# footswitch.net
KiCad netlist of a schematic drawn in EAGLE
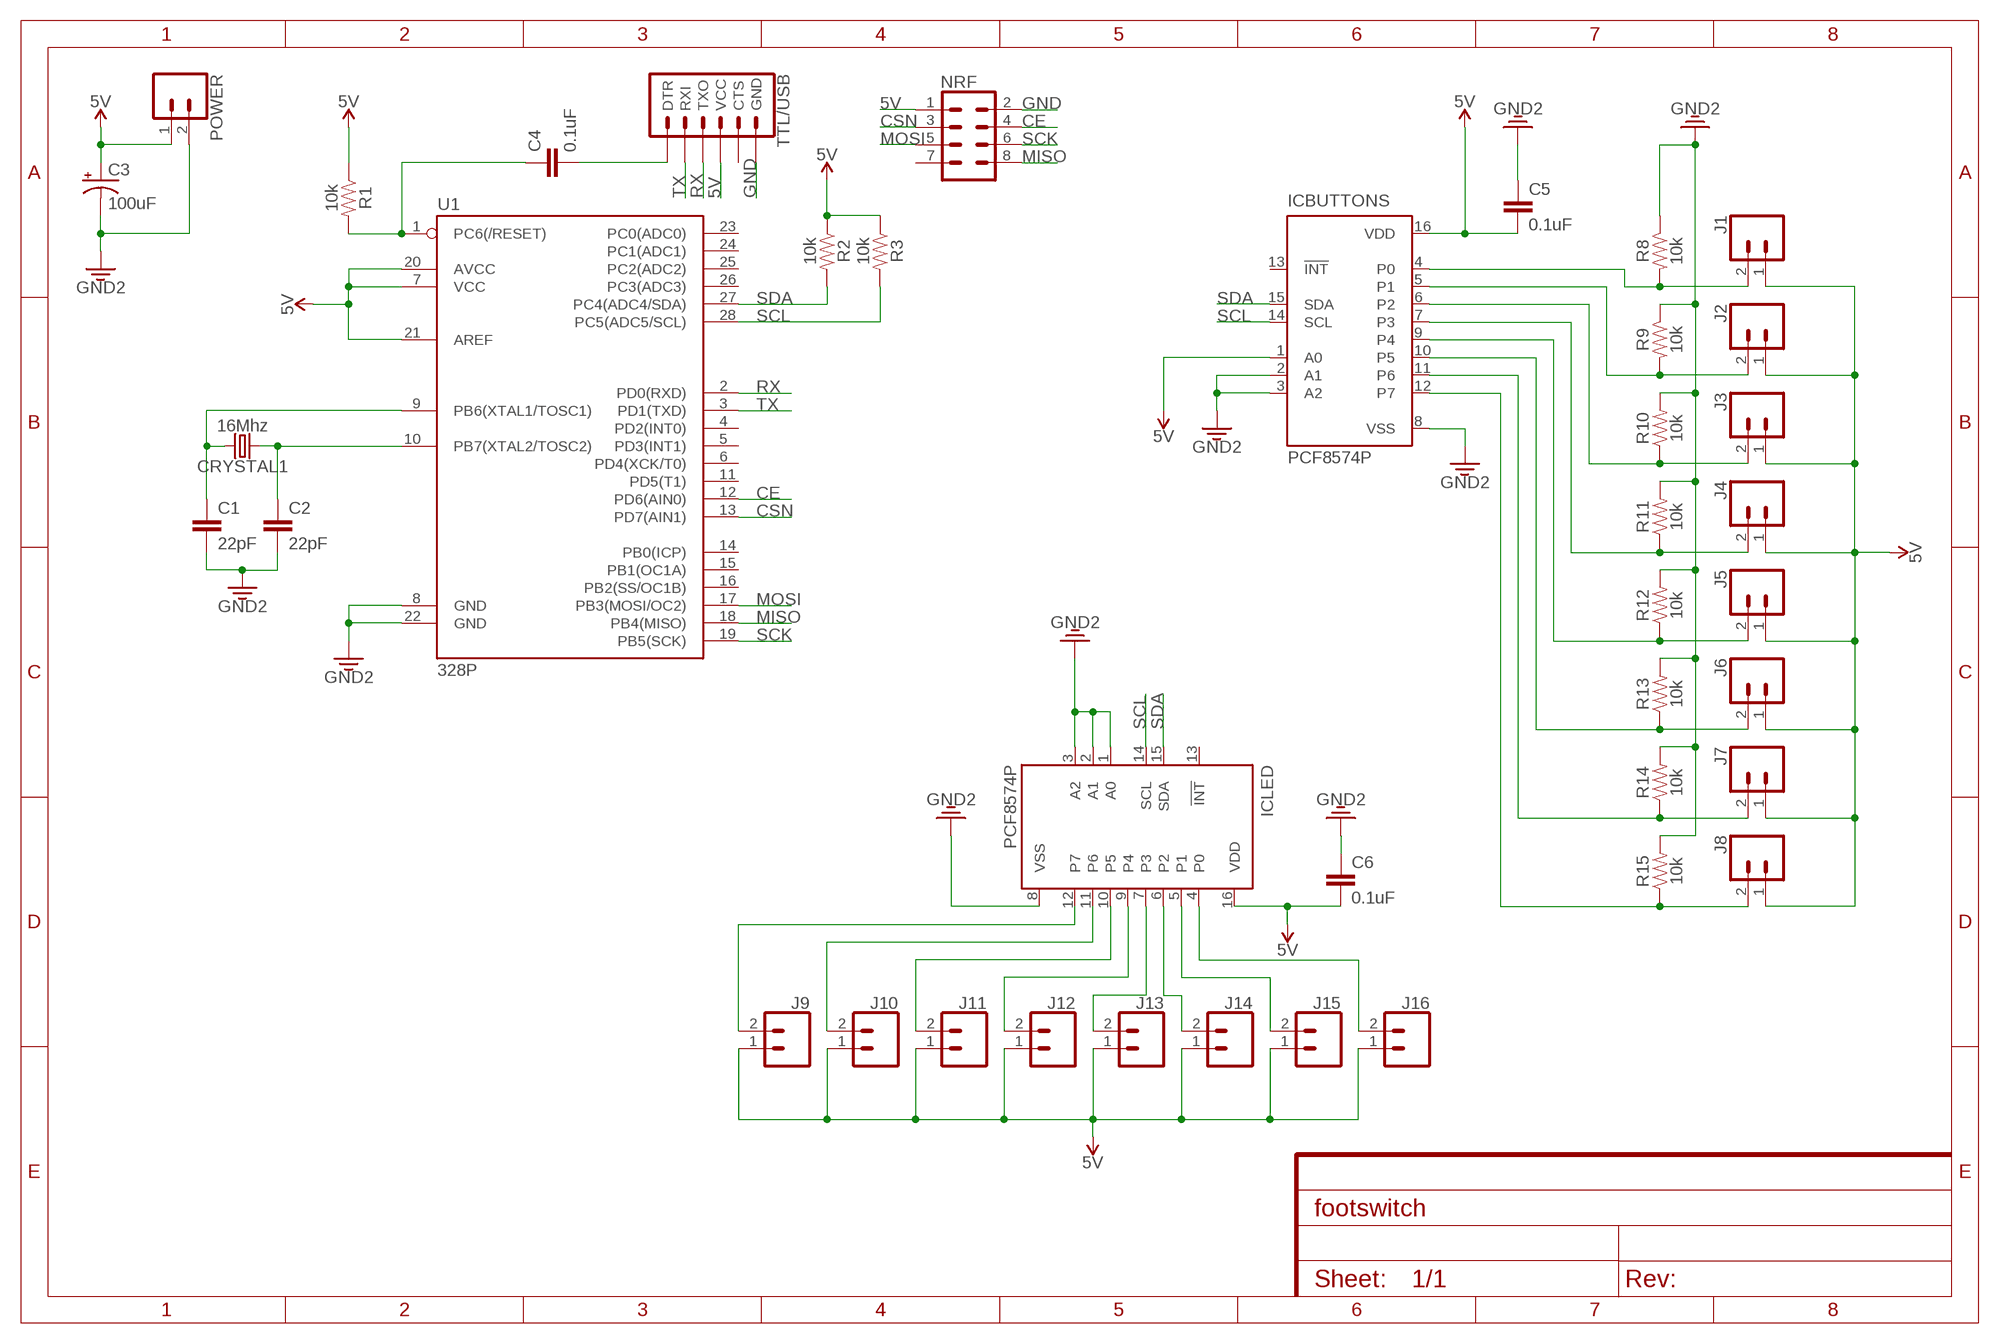
[diagram p0: schematic, sheet 1]

(export (version "E")
  (design (tool "Eeschema 10.0.6"))
  (components
    (comp (ref "C1")
      (value "22pF")
      (footprint "eagle-import:CAP-PTH-2.54")
      (libsource (lib "eagle-import") (part "22PF-PTH-2.54MM-200V-5%"))
    )
    (comp (ref "C2")
      (value "22pF")
      (footprint "eagle-import:CAP-PTH-2.54")
      (libsource (lib "eagle-import") (part "22PF-PTH-2.54MM-200V-5%"))
    )
    (comp (ref "C3")
      (value "100uF")
      (footprint "eagle-import:CPOL-RADIAL-2.5MM-6.5MM")
      (libsource (lib "eagle-import") (part "100UF-POLAR-RADIAL-2.5MM-25V-20%"))
    )
    (comp (ref "C4")
      (value "0.1uF")
      (footprint "eagle-import:CAP-PTH-SMALL-KIT")
      (libsource (lib "eagle-import") (part "0.1UF-KIT-EZ-50V-20%"))
    )
    (comp (ref "C5")
      (value "0.1uF")
      (footprint "eagle-import:CAP-PTH-SMALL-KIT")
      (libsource (lib "eagle-import") (part "0.1UF-KIT-EZ-50V-20%"))
    )
    (comp (ref "C6")
      (value "0.1uF")
      (footprint "eagle-import:CAP-PTH-SMALL-KIT")
      (libsource (lib "eagle-import") (part "0.1UF-KIT-EZ-50V-20%"))
    )
    (comp (ref "CRYSTAL1")
      (value "16Mhz")
      (footprint "eagle-import:HC49US")
      (libsource (lib "eagle-import") (part "CRYSTALPTH-HC49US"))
    )
    (comp (ref "ICBUTTONS")
      (value "PCF8574P")
      (footprint "eagle-import:DIL16")
      (fields (field (name "MPN") "PCF8574PN"))
      (libsource (lib "eagle-import") (part "PCF8574P"))
    )
    (comp (ref "ICLED")
      (value "PCF8574P")
      (footprint "eagle-import:DIL16")
      (fields (field (name "MPN") "PCF8574PN"))
      (libsource (lib "eagle-import") (part "PCF8574P"))
    )
    (comp (ref "J1")
      (value "CONN_02POLAR")
      (footprint "eagle-import:MOLEX-1X2")
      (libsource (lib "eagle-import") (part "CONN_02POLAR"))
    )
    (comp (ref "J2")
      (value "CONN_02POLAR")
      (footprint "eagle-import:MOLEX-1X2")
      (libsource (lib "eagle-import") (part "CONN_02POLAR"))
    )
    (comp (ref "J3")
      (value "CONN_02POLAR")
      (footprint "eagle-import:MOLEX-1X2")
      (libsource (lib "eagle-import") (part "CONN_02POLAR"))
    )
    (comp (ref "J4")
      (value "CONN_02POLAR")
      (footprint "eagle-import:MOLEX-1X2")
      (libsource (lib "eagle-import") (part "CONN_02POLAR"))
    )
    (comp (ref "J5")
      (value "CONN_02POLAR")
      (footprint "eagle-import:MOLEX-1X2")
      (libsource (lib "eagle-import") (part "CONN_02POLAR"))
    )
    (comp (ref "J6")
      (value "CONN_02POLAR")
      (footprint "eagle-import:MOLEX-1X2")
      (libsource (lib "eagle-import") (part "CONN_02POLAR"))
    )
    (comp (ref "J7")
      (value "CONN_02POLAR")
      (footprint "eagle-import:MOLEX-1X2")
      (libsource (lib "eagle-import") (part "CONN_02POLAR"))
    )
    (comp (ref "J8")
      (value "CONN_02POLAR")
      (footprint "eagle-import:MOLEX-1X2")
      (libsource (lib "eagle-import") (part "CONN_02POLAR"))
    )
    (comp (ref "J9")
      (value "CONN_02POLAR")
      (footprint "eagle-import:MOLEX-1X2")
      (libsource (lib "eagle-import") (part "CONN_02POLAR"))
    )
    (comp (ref "J10")
      (value "CONN_02POLAR")
      (footprint "eagle-import:MOLEX-1X2")
      (libsource (lib "eagle-import") (part "CONN_02POLAR"))
    )
    (comp (ref "J11")
      (value "CONN_02POLAR")
      (footprint "eagle-import:MOLEX-1X2")
      (libsource (lib "eagle-import") (part "CONN_02POLAR"))
    )
    (comp (ref "J12")
      (value "CONN_02POLAR")
      (footprint "eagle-import:MOLEX-1X2")
      (libsource (lib "eagle-import") (part "CONN_02POLAR"))
    )
    (comp (ref "J13")
      (value "CONN_02POLAR")
      (footprint "eagle-import:MOLEX-1X2")
      (libsource (lib "eagle-import") (part "CONN_02POLAR"))
    )
    (comp (ref "J14")
      (value "CONN_02POLAR")
      (footprint "eagle-import:MOLEX-1X2")
      (libsource (lib "eagle-import") (part "CONN_02POLAR"))
    )
    (comp (ref "J15")
      (value "CONN_02POLAR")
      (footprint "eagle-import:MOLEX-1X2")
      (libsource (lib "eagle-import") (part "CONN_02POLAR"))
    )
    (comp (ref "J16")
      (value "CONN_02POLAR")
      (footprint "eagle-import:MOLEX-1X2")
      (libsource (lib "eagle-import") (part "CONN_02POLAR"))
    )
    (comp (ref "NRF")
      (value "CONN_04X2")
      (footprint "eagle-import:2X4")
      (libsource (lib "eagle-import") (part "CONN_04X2"))
    )
    (comp (ref "POWER")
      (value "CONN_02")
      (footprint "eagle-import:1X02")
      (libsource (lib "eagle-import") (part "CONN_02"))
    )
    (comp (ref "R1")
      (value "10k")
      (footprint "eagle-import:AXIAL-0.3")
      (libsource (lib "eagle-import") (part "10KOHM-HORIZ-1/4W-1%"))
    )
    (comp (ref "R2")
      (value "10k")
      (footprint "eagle-import:AXIAL-0.3")
      (libsource (lib "eagle-import") (part "10KOHM-HORIZ-1/4W-1%"))
    )
    (comp (ref "R3")
      (value "10k")
      (footprint "eagle-import:AXIAL-0.3")
      (libsource (lib "eagle-import") (part "10KOHM-HORIZ-1/4W-1%"))
    )
    (comp (ref "R8")
      (value "10k")
      (footprint "eagle-import:AXIAL-0.3")
      (libsource (lib "eagle-import") (part "10KOHM-HORIZ-1/4W-1%"))
    )
    (comp (ref "R9")
      (value "10k")
      (footprint "eagle-import:AXIAL-0.3")
      (libsource (lib "eagle-import") (part "10KOHM-HORIZ-1/4W-1%"))
    )
    (comp (ref "R10")
      (value "10k")
      (footprint "eagle-import:AXIAL-0.3")
      (libsource (lib "eagle-import") (part "10KOHM-HORIZ-1/4W-1%"))
    )
    (comp (ref "R11")
      (value "10k")
      (footprint "eagle-import:AXIAL-0.3")
      (libsource (lib "eagle-import") (part "10KOHM-HORIZ-1/4W-1%"))
    )
    (comp (ref "R12")
      (value "10k")
      (footprint "eagle-import:AXIAL-0.3")
      (libsource (lib "eagle-import") (part "10KOHM-HORIZ-1/4W-1%"))
    )
    (comp (ref "R13")
      (value "10k")
      (footprint "eagle-import:AXIAL-0.3")
      (libsource (lib "eagle-import") (part "10KOHM-HORIZ-1/4W-1%"))
    )
    (comp (ref "R14")
      (value "10k")
      (footprint "eagle-import:AXIAL-0.3")
      (libsource (lib "eagle-import") (part "10KOHM-HORIZ-1/4W-1%"))
    )
    (comp (ref "R15")
      (value "10k")
      (footprint "eagle-import:AXIAL-0.3")
      (libsource (lib "eagle-import") (part "10KOHM-HORIZ-1/4W-1%"))
    )
    (comp (ref "TTL/USB")
      (value "6_PIN_SERIAL_TARGETPTH-KIT")
      (footprint "eagle-import:1X06-KIT")
      (libsource (lib "eagle-import") (part "6_PIN_SERIAL_TARGETPTH-KIT"))
    )
    (comp (ref "U1")
      (value "328P")
      (footprint "eagle-import:DIP28")
      (libsource (lib "eagle-import") (part "ATMEGA328P_PDIP"))
    )
  )
  (nets
    (net (code "1") (name "/CE") (class "Default")
      (node (ref "NRF") (pin "4") (pinfunction "4_4") (pintype "passive"))
      (node (ref "U1") (pin "12") (pinfunction "PD6(AIN0)_12") (pintype "bidirectional"))
    )
    (net (code "2") (name "/CSN") (class "Default")
      (node (ref "NRF") (pin "3") (pinfunction "3_3") (pintype "passive"))
      (node (ref "U1") (pin "13") (pinfunction "PD7(AIN1)_13") (pintype "bidirectional"))
    )
    (net (code "3") (name "/MISO") (class "Default")
      (node (ref "NRF") (pin "8") (pinfunction "8_8") (pintype "passive"))
      (node (ref "U1") (pin "18") (pinfunction "PB4(MISO)_18") (pintype "bidirectional"))
    )
    (net (code "4") (name "/MOSI") (class "Default")
      (node (ref "NRF") (pin "5") (pinfunction "5_5") (pintype "passive"))
      (node (ref "U1") (pin "17") (pinfunction "PB3(MOSI/OC2)_17") (pintype "bidirectional"))
    )
    (net (code "5") (name "/RX") (class "Default")
      (node (ref "TTL/USB") (pin "3") (pinfunction "TXO_3") (pintype "passive"))
      (node (ref "U1") (pin "2") (pinfunction "PD0(RXD)_2") (pintype "bidirectional"))
    )
    (net (code "6") (name "/SCK") (class "Default")
      (node (ref "NRF") (pin "6") (pinfunction "6_6") (pintype "passive"))
      (node (ref "U1") (pin "19") (pinfunction "PB5(SCK)_19") (pintype "bidirectional"))
    )
    (net (code "7") (name "/SCL") (class "Default")
      (node (ref "ICBUTTONS") (pin "14") (pinfunction "SCL_14") (pintype "input"))
      (node (ref "ICLED") (pin "14") (pinfunction "SCL_14") (pintype "input"))
      (node (ref "R3") (pin "P$2") (pinfunction "2_P$2") (pintype "passive"))
      (node (ref "U1") (pin "28") (pinfunction "PC5(ADC5/SCL)_28") (pintype "bidirectional"))
    )
    (net (code "8") (name "/SDA") (class "Default")
      (node (ref "ICBUTTONS") (pin "15") (pinfunction "SDA_15") (pintype "bidirectional"))
      (node (ref "ICLED") (pin "15") (pinfunction "SDA_15") (pintype "bidirectional"))
      (node (ref "R2") (pin "P$2") (pinfunction "2_P$2") (pintype "passive"))
      (node (ref "U1") (pin "27") (pinfunction "PC4(ADC4/SDA)_27") (pintype "bidirectional"))
    )
    (net (code "9") (name "/TX") (class "Default")
      (node (ref "TTL/USB") (pin "2") (pinfunction "RXI_2") (pintype "passive"))
      (node (ref "U1") (pin "3") (pinfunction "PD1(TXD)_3") (pintype "bidirectional"))
    )
    (net (code "10") (name "5V") (class "Default")
      (node (ref "C3") (pin "1") (pinfunction "+_1") (pintype "passive"))
      (node (ref "C5") (pin "2") (pinfunction "2_2") (pintype "passive"))
      (node (ref "C6") (pin "2") (pinfunction "2_2") (pintype "passive"))
      (node (ref "ICBUTTONS") (pin "1") (pinfunction "A0_1") (pintype "input"))
      (node (ref "ICBUTTONS") (pin "16") (pinfunction "VDD_16") (pintype "power_in"))
      (node (ref "ICLED") (pin "16") (pinfunction "VDD_16") (pintype "power_in"))
      (node (ref "J1") (pin "1") (pinfunction "1_1") (pintype "passive"))
      (node (ref "J10") (pin "1") (pinfunction "1_1") (pintype "passive"))
      (node (ref "J11") (pin "1") (pinfunction "1_1") (pintype "passive"))
      (node (ref "J12") (pin "1") (pinfunction "1_1") (pintype "passive"))
      (node (ref "J13") (pin "1") (pinfunction "1_1") (pintype "passive"))
      (node (ref "J14") (pin "1") (pinfunction "1_1") (pintype "passive"))
      (node (ref "J15") (pin "1") (pinfunction "1_1") (pintype "passive"))
      (node (ref "J16") (pin "1") (pinfunction "1_1") (pintype "passive"))
      (node (ref "J2") (pin "1") (pinfunction "1_1") (pintype "passive"))
      (node (ref "J3") (pin "1") (pinfunction "1_1") (pintype "passive"))
      (node (ref "J4") (pin "1") (pinfunction "1_1") (pintype "passive"))
      (node (ref "J5") (pin "1") (pinfunction "1_1") (pintype "passive"))
      (node (ref "J6") (pin "1") (pinfunction "1_1") (pintype "passive"))
      (node (ref "J7") (pin "1") (pinfunction "1_1") (pintype "passive"))
      (node (ref "J8") (pin "1") (pinfunction "1_1") (pintype "passive"))
      (node (ref "J9") (pin "1") (pinfunction "1_1") (pintype "passive"))
      (node (ref "NRF") (pin "1") (pinfunction "1_1") (pintype "passive"))
      (node (ref "POWER") (pin "1") (pinfunction "1_1") (pintype "passive"))
      (node (ref "R1") (pin "P$1") (pinfunction "1_P$1") (pintype "passive"))
      (node (ref "R2") (pin "P$1") (pinfunction "1_P$1") (pintype "passive"))
      (node (ref "R3") (pin "P$1") (pinfunction "1_P$1") (pintype "passive"))
      (node (ref "TTL/USB") (pin "4") (pinfunction "VCC_4") (pintype "passive"))
      (node (ref "U1") (pin "20") (pinfunction "AVCC_20") (pintype "bidirectional"))
      (node (ref "U1") (pin "21") (pinfunction "AREF_21") (pintype "bidirectional"))
      (node (ref "U1") (pin "7") (pinfunction "VCC_7") (pintype "bidirectional"))
    )
    (net (code "11") (name "GND2") (class "Default")
      (node (ref "C1") (pin "2") (pinfunction "2_2") (pintype "passive"))
      (node (ref "C2") (pin "2") (pinfunction "2_2") (pintype "passive"))
      (node (ref "C3") (pin "2") (pinfunction "-_2") (pintype "passive"))
      (node (ref "C5") (pin "1") (pinfunction "1_1") (pintype "passive"))
      (node (ref "C6") (pin "1") (pinfunction "1_1") (pintype "passive"))
      (node (ref "ICBUTTONS") (pin "2") (pinfunction "A1_2") (pintype "input"))
      (node (ref "ICBUTTONS") (pin "3") (pinfunction "A2_3") (pintype "input"))
      (node (ref "ICBUTTONS") (pin "8") (pinfunction "VSS_8") (pintype "power_in"))
      (node (ref "ICLED") (pin "1") (pinfunction "A0_1") (pintype "input"))
      (node (ref "ICLED") (pin "2") (pinfunction "A1_2") (pintype "input"))
      (node (ref "ICLED") (pin "3") (pinfunction "A2_3") (pintype "input"))
      (node (ref "ICLED") (pin "8") (pinfunction "VSS_8") (pintype "power_in"))
      (node (ref "NRF") (pin "2") (pinfunction "2_2") (pintype "passive"))
      (node (ref "POWER") (pin "2") (pinfunction "2_2") (pintype "passive"))
      (node (ref "R10") (pin "P$2") (pinfunction "2_P$2") (pintype "passive"))
      (node (ref "R11") (pin "P$2") (pinfunction "2_P$2") (pintype "passive"))
      (node (ref "R12") (pin "P$2") (pinfunction "2_P$2") (pintype "passive"))
      (node (ref "R13") (pin "P$2") (pinfunction "2_P$2") (pintype "passive"))
      (node (ref "R14") (pin "P$2") (pinfunction "2_P$2") (pintype "passive"))
      (node (ref "R15") (pin "P$2") (pinfunction "2_P$2") (pintype "passive"))
      (node (ref "R8") (pin "P$1") (pinfunction "1_P$1") (pintype "passive"))
      (node (ref "R9") (pin "P$1") (pinfunction "1_P$1") (pintype "passive"))
      (node (ref "TTL/USB") (pin "6") (pinfunction "GND_6") (pintype "passive"))
      (node (ref "U1") (pin "22") (pinfunction "GND_22") (pintype "bidirectional"))
      (node (ref "U1") (pin "8") (pinfunction "GND_8") (pintype "bidirectional"))
    )
    (net (code "12") (name "Net-(ICBUTTONS-P0)") (class "Default")
      (node (ref "ICBUTTONS") (pin "4") (pinfunction "P0_4") (pintype "bidirectional"))
      (node (ref "J1") (pin "2") (pinfunction "2_2") (pintype "passive"))
      (node (ref "R8") (pin "P$2") (pinfunction "2_P$2") (pintype "passive"))
    )
    (net (code "13") (name "Net-(ICBUTTONS-P1)") (class "Default")
      (node (ref "ICBUTTONS") (pin "5") (pinfunction "P1_5") (pintype "bidirectional"))
      (node (ref "J2") (pin "2") (pinfunction "2_2") (pintype "passive"))
      (node (ref "R9") (pin "P$2") (pinfunction "2_P$2") (pintype "passive"))
    )
    (net (code "14") (name "Net-(ICBUTTONS-P2)") (class "Default")
      (node (ref "ICBUTTONS") (pin "6") (pinfunction "P2_6") (pintype "bidirectional"))
      (node (ref "J3") (pin "2") (pinfunction "2_2") (pintype "passive"))
      (node (ref "R10") (pin "P$1") (pinfunction "1_P$1") (pintype "passive"))
    )
    (net (code "15") (name "Net-(ICBUTTONS-P3)") (class "Default")
      (node (ref "ICBUTTONS") (pin "7") (pinfunction "P3_7") (pintype "bidirectional"))
      (node (ref "J4") (pin "2") (pinfunction "2_2") (pintype "passive"))
      (node (ref "R11") (pin "P$1") (pinfunction "1_P$1") (pintype "passive"))
    )
    (net (code "16") (name "Net-(ICBUTTONS-P4)") (class "Default")
      (node (ref "ICBUTTONS") (pin "9") (pinfunction "P4_9") (pintype "bidirectional"))
      (node (ref "J5") (pin "2") (pinfunction "2_2") (pintype "passive"))
      (node (ref "R12") (pin "P$1") (pinfunction "1_P$1") (pintype "passive"))
    )
    (net (code "17") (name "Net-(ICBUTTONS-P5)") (class "Default")
      (node (ref "ICBUTTONS") (pin "10") (pinfunction "P5_10") (pintype "bidirectional"))
      (node (ref "J6") (pin "2") (pinfunction "2_2") (pintype "passive"))
      (node (ref "R13") (pin "P$1") (pinfunction "1_P$1") (pintype "passive"))
    )
    (net (code "18") (name "Net-(ICBUTTONS-P6)") (class "Default")
      (node (ref "ICBUTTONS") (pin "11") (pinfunction "P6_11") (pintype "bidirectional"))
      (node (ref "J7") (pin "2") (pinfunction "2_2") (pintype "passive"))
      (node (ref "R14") (pin "P$1") (pinfunction "1_P$1") (pintype "passive"))
    )
    (net (code "19") (name "Net-(ICBUTTONS-P7)") (class "Default")
      (node (ref "ICBUTTONS") (pin "12") (pinfunction "P7_12") (pintype "bidirectional"))
      (node (ref "J8") (pin "2") (pinfunction "2_2") (pintype "passive"))
      (node (ref "R15") (pin "P$1") (pinfunction "1_P$1") (pintype "passive"))
    )
    (net (code "20") (name "Net-(ICLED-P0)") (class "Default")
      (node (ref "ICLED") (pin "4") (pinfunction "P0_4") (pintype "bidirectional"))
      (node (ref "J16") (pin "2") (pinfunction "2_2") (pintype "passive"))
    )
    (net (code "21") (name "Net-(ICLED-P1)") (class "Default")
      (node (ref "ICLED") (pin "5") (pinfunction "P1_5") (pintype "bidirectional"))
      (node (ref "J15") (pin "2") (pinfunction "2_2") (pintype "passive"))
    )
    (net (code "22") (name "Net-(ICLED-P2)") (class "Default")
      (node (ref "ICLED") (pin "6") (pinfunction "P2_6") (pintype "bidirectional"))
      (node (ref "J14") (pin "2") (pinfunction "2_2") (pintype "passive"))
    )
    (net (code "23") (name "Net-(ICLED-P3)") (class "Default")
      (node (ref "ICLED") (pin "7") (pinfunction "P3_7") (pintype "bidirectional"))
      (node (ref "J13") (pin "2") (pinfunction "2_2") (pintype "passive"))
    )
    (net (code "24") (name "Net-(ICLED-P4)") (class "Default")
      (node (ref "ICLED") (pin "9") (pinfunction "P4_9") (pintype "bidirectional"))
      (node (ref "J12") (pin "2") (pinfunction "2_2") (pintype "passive"))
    )
    (net (code "25") (name "Net-(ICLED-P5)") (class "Default")
      (node (ref "ICLED") (pin "10") (pinfunction "P5_10") (pintype "bidirectional"))
      (node (ref "J11") (pin "2") (pinfunction "2_2") (pintype "passive"))
    )
    (net (code "26") (name "Net-(ICLED-P6)") (class "Default")
      (node (ref "ICLED") (pin "11") (pinfunction "P6_11") (pintype "bidirectional"))
      (node (ref "J10") (pin "2") (pinfunction "2_2") (pintype "passive"))
    )
    (net (code "27") (name "Net-(ICLED-P7)") (class "Default")
      (node (ref "ICLED") (pin "12") (pinfunction "P7_12") (pintype "bidirectional"))
      (node (ref "J9") (pin "2") (pinfunction "2_2") (pintype "passive"))
    )
    (net (code "28") (name "Net-(R1-2)") (class "Default")
      (node (ref "C4") (pin "1") (pinfunction "1_1") (pintype "passive"))
      (node (ref "R1") (pin "P$2") (pinfunction "2_P$2") (pintype "passive"))
      (node (ref "U1") (pin "1") (pinfunction "PC6(/RESET)_1") (pintype "bidirectional"))
    )
    (net (code "29") (name "Net-(TTL/USB-DTR)") (class "Default")
      (node (ref "C4") (pin "2") (pinfunction "2_2") (pintype "passive"))
      (node (ref "TTL/USB") (pin "1") (pinfunction "DTR_1") (pintype "passive"))
    )
    (net (code "30") (name "Net-(U1-PB6(XTAL1{slash}TOSC1))") (class "Default")
      (node (ref "C1") (pin "1") (pinfunction "1_1") (pintype "passive"))
      (node (ref "CRYSTAL1") (pin "2") (pinfunction "2_2") (pintype "passive"))
      (node (ref "U1") (pin "9") (pinfunction "PB6(XTAL1/TOSC1)_9") (pintype "bidirectional"))
    )
    (net (code "31") (name "Net-(U1-PB7(XTAL2{slash}TOSC2))") (class "Default")
      (node (ref "C2") (pin "1") (pinfunction "1_1") (pintype "passive"))
      (node (ref "CRYSTAL1") (pin "1") (pinfunction "1_1") (pintype "passive"))
      (node (ref "U1") (pin "10") (pinfunction "PB7(XTAL2/TOSC2)_10") (pintype "bidirectional"))
    )
    (net (code "32") (name "unconnected-(ICBUTTONS-~{INT}-Pad13)") (class "Default")
      (node (ref "ICBUTTONS") (pin "13") (pinfunction "~{INT}_13") (pintype "output"))
    )
    (net (code "33") (name "unconnected-(ICLED-~{INT}-Pad13)") (class "Default")
      (node (ref "ICLED") (pin "13") (pinfunction "~{INT}_13") (pintype "output"))
    )
    (net (code "34") (name "unconnected-(NRF-Pad7)") (class "Default")
      (node (ref "NRF") (pin "7") (pinfunction "7_7") (pintype "passive"))
    )
    (net (code "35") (name "unconnected-(TTL/USB-CTS-Pad5)") (class "Default")
      (node (ref "TTL/USB") (pin "5") (pinfunction "CTS_5") (pintype "passive"))
    )
    (net (code "36") (name "unconnected-(U1-PB0(ICP)-Pad14)") (class "Default")
      (node (ref "U1") (pin "14") (pinfunction "PB0(ICP)_14") (pintype "bidirectional"))
    )
    (net (code "37") (name "unconnected-(U1-PB1(OC1A)-Pad15)") (class "Default")
      (node (ref "U1") (pin "15") (pinfunction "PB1(OC1A)_15") (pintype "bidirectional"))
    )
    (net (code "38") (name "unconnected-(U1-PB2(SS{slash}OC1B)-Pad16)") (class "Default")
      (node (ref "U1") (pin "16") (pinfunction "PB2(SS/OC1B)_16") (pintype "bidirectional"))
    )
    (net (code "39") (name "unconnected-(U1-PC0(ADC0)-Pad23)") (class "Default")
      (node (ref "U1") (pin "23") (pinfunction "PC0(ADC0)_23") (pintype "bidirectional"))
    )
    (net (code "40") (name "unconnected-(U1-PC1(ADC1)-Pad24)") (class "Default")
      (node (ref "U1") (pin "24") (pinfunction "PC1(ADC1)_24") (pintype "bidirectional"))
    )
    (net (code "41") (name "unconnected-(U1-PC2(ADC2)-Pad25)") (class "Default")
      (node (ref "U1") (pin "25") (pinfunction "PC2(ADC2)_25") (pintype "bidirectional"))
    )
    (net (code "42") (name "unconnected-(U1-PC3(ADC3)-Pad26)") (class "Default")
      (node (ref "U1") (pin "26") (pinfunction "PC3(ADC3)_26") (pintype "bidirectional"))
    )
    (net (code "43") (name "unconnected-(U1-PD2(INT0)-Pad4)") (class "Default")
      (node (ref "U1") (pin "4") (pinfunction "PD2(INT0)_4") (pintype "bidirectional"))
    )
    (net (code "44") (name "unconnected-(U1-PD3(INT1)-Pad5)") (class "Default")
      (node (ref "U1") (pin "5") (pinfunction "PD3(INT1)_5") (pintype "bidirectional"))
    )
    (net (code "45") (name "unconnected-(U1-PD4(XCK{slash}T0)-Pad6)") (class "Default")
      (node (ref "U1") (pin "6") (pinfunction "PD4(XCK/T0)_6") (pintype "bidirectional"))
    )
    (net (code "46") (name "unconnected-(U1-PD5(T1)-Pad11)") (class "Default")
      (node (ref "U1") (pin "11") (pinfunction "PD5(T1)_11") (pintype "bidirectional"))
    )
  )
)
